# stc8g.net
KiCad netlist of a schematic drawn in EasyEDA Pro
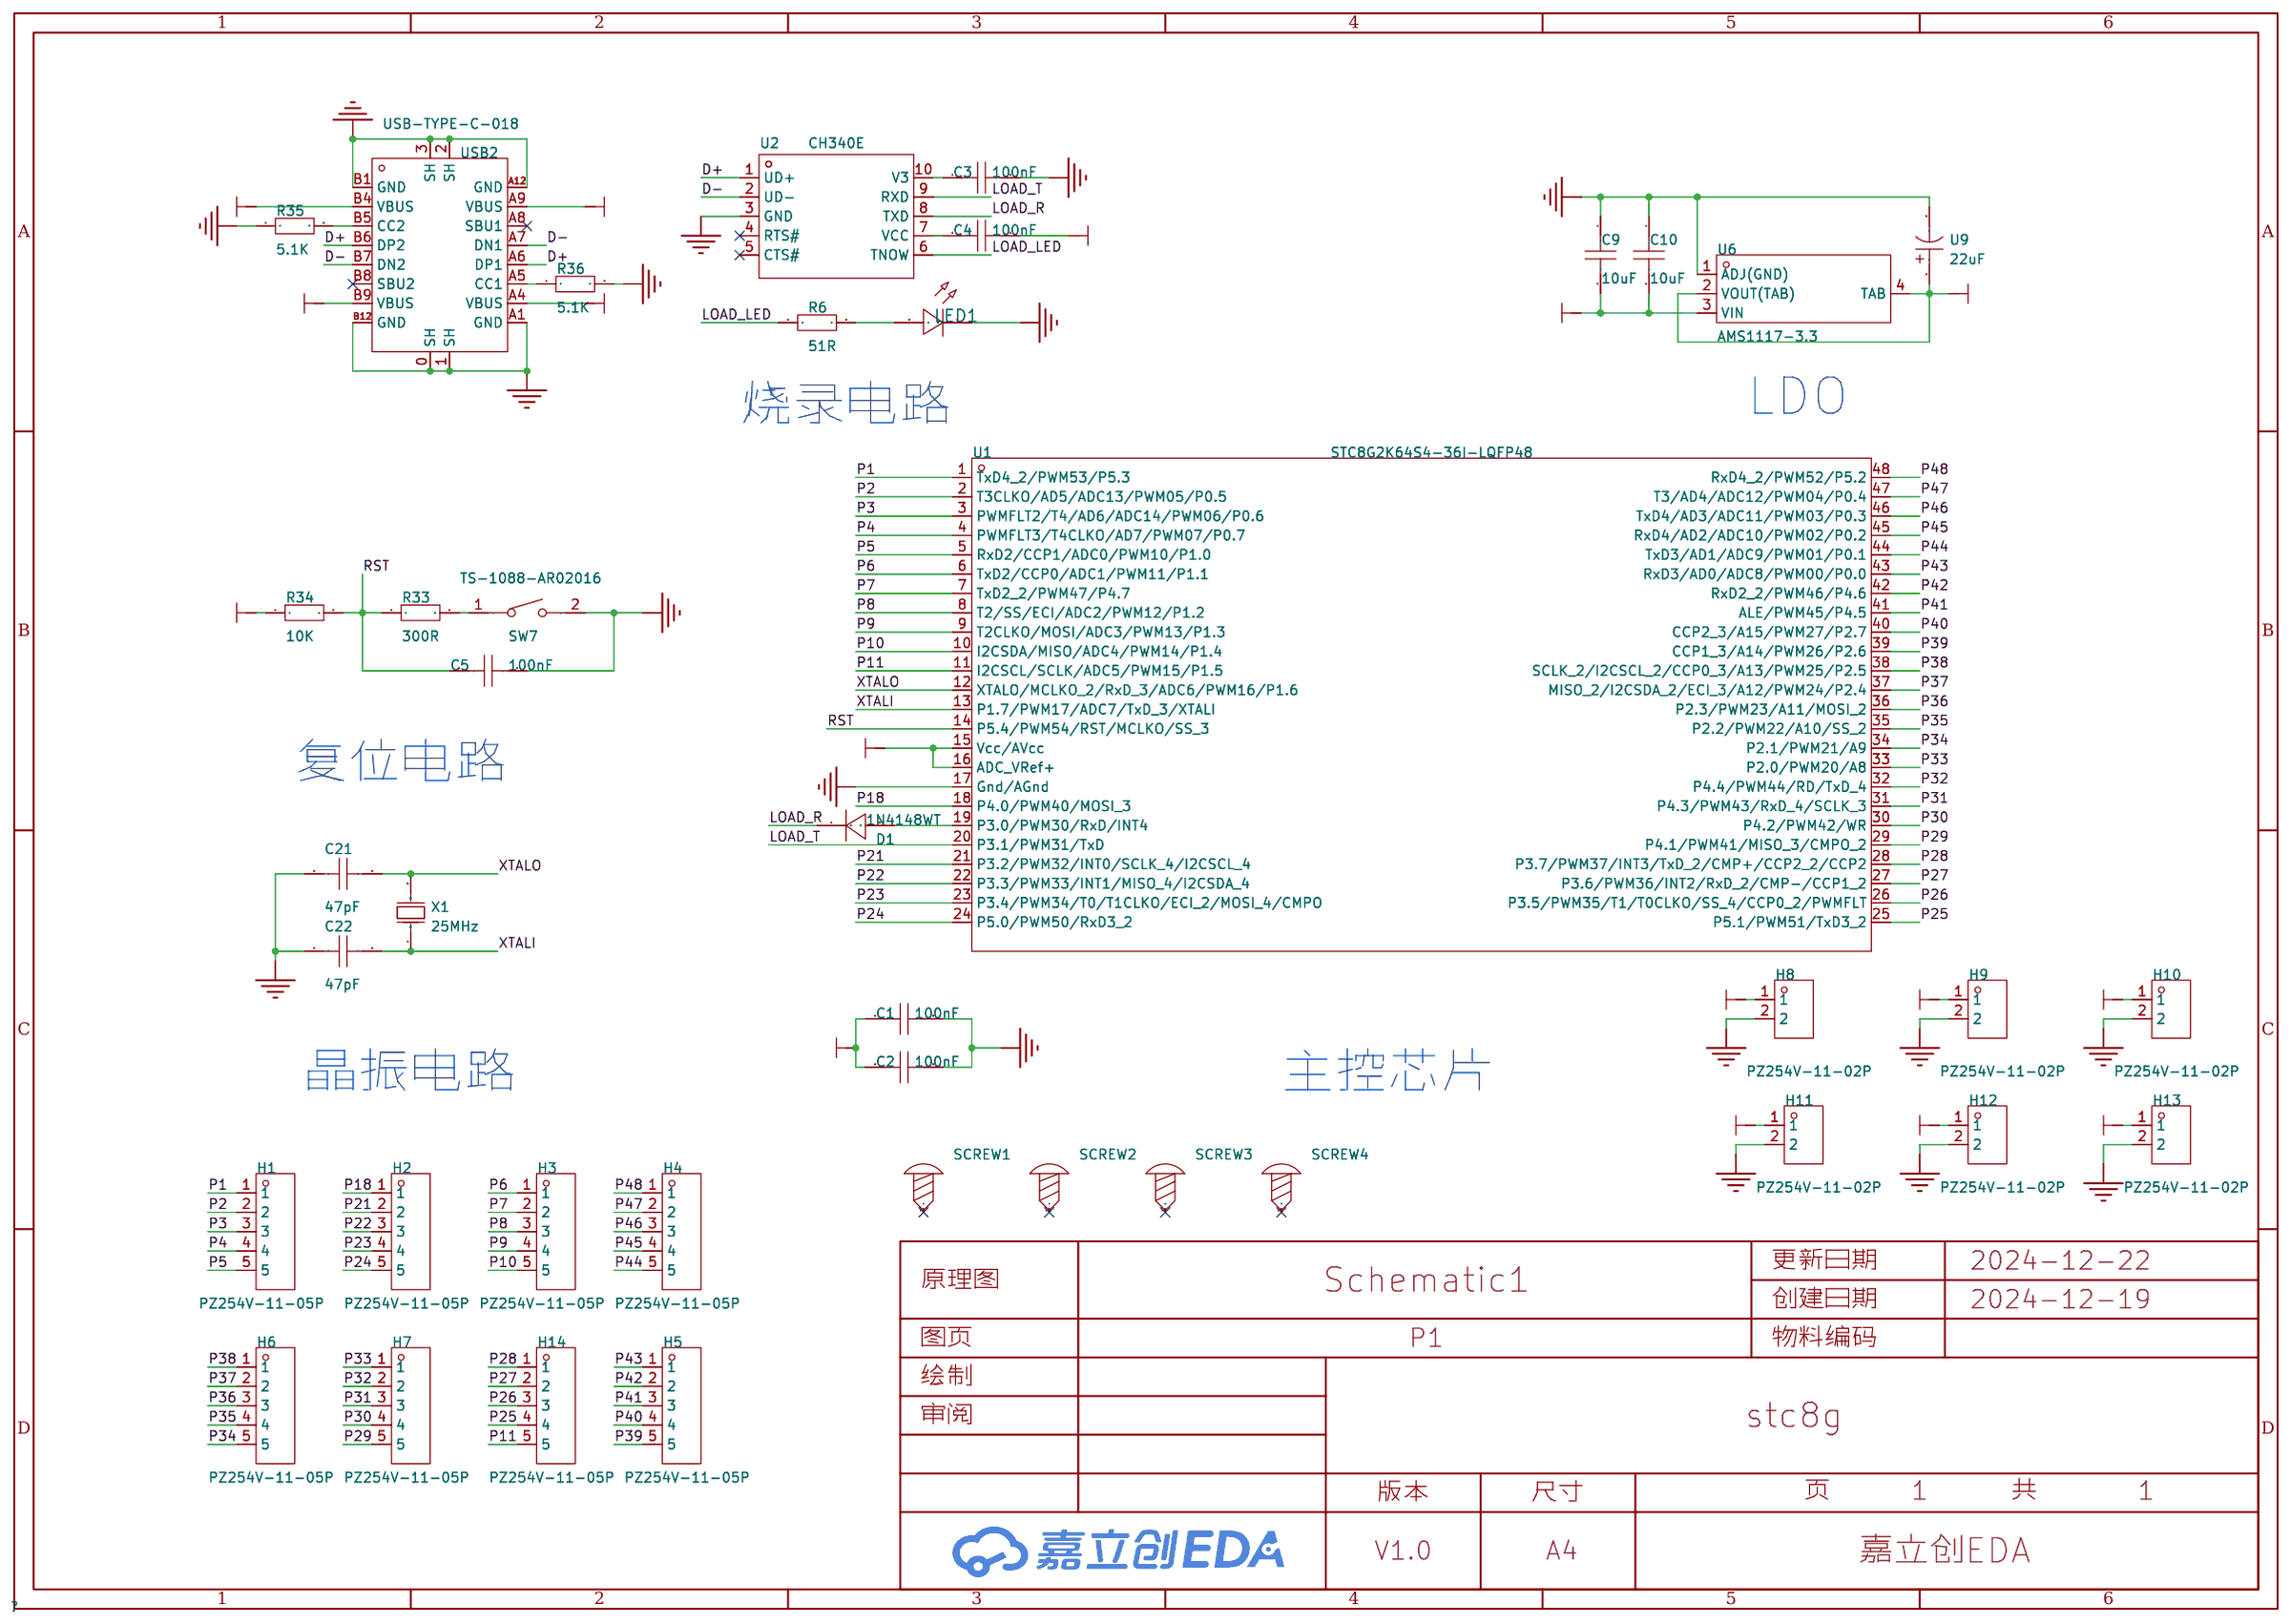
[diagram p0: schematic sheet]

(export (version "E")
  (design (tool "Eeschema 10.0.6"))
  (components
    (comp (ref "C1")
      (value "100nF")
      (footprint "easyedapro:C0603")
      (libsource (lib "easyedapro") (part "CapAcitance"))
    )
    (comp (ref "C2")
      (value "100nF")
      (footprint "easyedapro:C0603")
      (libsource (lib "easyedapro") (part "CapAcitance"))
    )
    (comp (ref "C3")
      (value "100nF")
      (footprint "easyedapro:C0603")
      (libsource (lib "easyedapro") (part "CapAcitance"))
    )
    (comp (ref "C4")
      (value "100nF")
      (footprint "easyedapro:C0603")
      (libsource (lib "easyedapro") (part "CapAcitance"))
    )
    (comp (ref "C5")
      (value "100nF")
      (footprint "easyedapro:C0603")
      (libsource (lib "easyedapro") (part "CapAcitance"))
    )
    (comp (ref "C9")
      (value "10uF")
      (footprint "easyedapro:C0603")
      (libsource (lib "easyedapro") (part "CapAcitance"))
    )
    (comp (ref "C10")
      (value "10uF")
      (footprint "easyedapro:C0603")
      (libsource (lib "easyedapro") (part "CapAcitance"))
    )
    (comp (ref "C21")
      (value "47pF")
      (footprint "easyedapro:C0603")
      (libsource (lib "easyedapro") (part "CapAcitance"))
    )
    (comp (ref "C22")
      (value "47pF")
      (footprint "easyedapro:C0603")
      (libsource (lib "easyedapro") (part "CapAcitance"))
    )
    (comp (ref "D1")
      (value "1N4148WT")
      (footprint "easyedapro:SOD-523_L1.2-W0.8-LS1.6-RD")
      (description "二极管配置:独立式;正向压降(Vf):1V@10mA;直流反向耐压(Vr):75V;平均整流电流(Io):300mA;功率:200mW;反向恢复时间(trr):4ns;")
      (fields (field (name "Manufacturer") "onsemi(安森美)"))
      (libsource (lib "easyedapro") (part "1N4148WT_C232841"))
    )
    (comp (ref "H1")
      (value "PZ254V-11-05P")
      (footprint "easyedapro:HDR-TH_5P-P2.54-V-M")
      (fields (field (name "Manufacturer") "XFCN(兴飞)"))
      (libsource (lib "easyedapro") (part "PZ254V-11-05P"))
    )
    (comp (ref "H2")
      (value "PZ254V-11-05P")
      (footprint "easyedapro:HDR-TH_5P-P2.54-V-M")
      (fields (field (name "Manufacturer") "XFCN(兴飞)"))
      (libsource (lib "easyedapro") (part "PZ254V-11-05P"))
    )
    (comp (ref "H3")
      (value "PZ254V-11-05P")
      (footprint "easyedapro:HDR-TH_5P-P2.54-V-M")
      (fields (field (name "Manufacturer") "XFCN(兴飞)"))
      (libsource (lib "easyedapro") (part "PZ254V-11-05P"))
    )
    (comp (ref "H4")
      (value "PZ254V-11-05P")
      (footprint "easyedapro:HDR-TH_5P-P2.54-V-M")
      (fields (field (name "Manufacturer") "XFCN(兴飞)"))
      (libsource (lib "easyedapro") (part "PZ254V-11-05P"))
    )
    (comp (ref "H5")
      (value "PZ254V-11-05P")
      (footprint "easyedapro:HDR-TH_5P-P2.54-V-M")
      (fields (field (name "Manufacturer") "XFCN(兴飞)"))
      (libsource (lib "easyedapro") (part "PZ254V-11-05P"))
    )
    (comp (ref "H6")
      (value "PZ254V-11-05P")
      (footprint "easyedapro:HDR-TH_5P-P2.54-V-M")
      (fields (field (name "Manufacturer") "XFCN(兴飞)"))
      (libsource (lib "easyedapro") (part "PZ254V-11-05P"))
    )
    (comp (ref "H7")
      (value "PZ254V-11-05P")
      (footprint "easyedapro:HDR-TH_5P-P2.54-V-M")
      (fields (field (name "Manufacturer") "XFCN(兴飞)"))
      (libsource (lib "easyedapro") (part "PZ254V-11-05P"))
    )
    (comp (ref "H8")
      (value "PZ254V-11-02P")
      (footprint "easyedapro:HDR-TH_2P-P2.54-V-M")
      (fields (field (name "Manufacturer") "XFCN(兴飞)"))
      (libsource (lib "easyedapro") (part "PZ254V-11-02P"))
    )
    (comp (ref "H9")
      (value "PZ254V-11-02P")
      (footprint "easyedapro:HDR-TH_2P-P2.54-V-M")
      (fields (field (name "Manufacturer") "XFCN(兴飞)"))
      (libsource (lib "easyedapro") (part "PZ254V-11-02P"))
    )
    (comp (ref "H10")
      (value "PZ254V-11-02P")
      (footprint "easyedapro:HDR-TH_2P-P2.54-V-M")
      (fields (field (name "Manufacturer") "XFCN(兴飞)"))
      (libsource (lib "easyedapro") (part "PZ254V-11-02P"))
    )
    (comp (ref "H11")
      (value "PZ254V-11-02P")
      (footprint "easyedapro:HDR-TH_2P-P2.54-V-M")
      (fields (field (name "Manufacturer") "XFCN(兴飞)"))
      (libsource (lib "easyedapro") (part "PZ254V-11-02P"))
    )
    (comp (ref "H12")
      (value "PZ254V-11-02P")
      (footprint "easyedapro:HDR-TH_2P-P2.54-V-M")
      (fields (field (name "Manufacturer") "XFCN(兴飞)"))
      (libsource (lib "easyedapro") (part "PZ254V-11-02P"))
    )
    (comp (ref "H13")
      (value "PZ254V-11-02P")
      (footprint "easyedapro:HDR-TH_2P-P2.54-V-M")
      (fields (field (name "Manufacturer") "XFCN(兴飞)"))
      (libsource (lib "easyedapro") (part "PZ254V-11-02P"))
    )
    (comp (ref "H14")
      (value "PZ254V-11-05P")
      (footprint "easyedapro:HDR-TH_5P-P2.54-V-M")
      (fields (field (name "Manufacturer") "XFCN(兴飞)"))
      (libsource (lib "easyedapro") (part "PZ254V-11-05P"))
    )
    (comp (ref "LED1")
      (value "~")
      (footprint "easyedapro:LED_0603")
      (libsource (lib "easyedapro") (part "LED_R"))
    )
    (comp (ref "R6") (value "51R") (footprint "easyedapro:R0603") (libsource (lib "easyedapro") (part "电阻")))
    (comp (ref "R33")
      (value "300R")
      (footprint "easyedapro:R0603")
      (libsource (lib "easyedapro") (part "电阻"))
    )
    (comp (ref "R34") (value "10K") (footprint "easyedapro:R0603") (libsource (lib "easyedapro") (part "电阻")))
    (comp (ref "R35")
      (value "5.1K")
      (footprint "easyedapro:R0603")
      (libsource (lib "easyedapro") (part "电阻"))
    )
    (comp (ref "R36")
      (value "5.1K")
      (footprint "easyedapro:R0603")
      (libsource (lib "easyedapro") (part "电阻"))
    )
    (comp (ref "SCREW1")
      (value "~")
      (footprint "easyedapro:M2螺丝")
      (libsource (lib "easyedapro") (part "螺丝孔"))
    )
    (comp (ref "SCREW2")
      (value "~")
      (footprint "easyedapro:M2螺丝")
      (libsource (lib "easyedapro") (part "螺丝孔"))
    )
    (comp (ref "SCREW3")
      (value "~")
      (footprint "easyedapro:M2螺丝")
      (libsource (lib "easyedapro") (part "螺丝孔"))
    )
    (comp (ref "SCREW4")
      (value "~")
      (footprint "easyedapro:M2螺丝")
      (libsource (lib "easyedapro") (part "螺丝孔"))
    )
    (comp (ref "SW7")
      (value "TS-1088-AR02016")
      (footprint "easyedapro:SW-SMD_L3.9-W3.0-P4.45")
      (fields (field (name "Manufacturer") "XUNPU(讯普)"))
      (libsource (lib "easyedapro") (part "TS-1088-AR02016"))
    )
    (comp (ref "U1")
      (value "STC8G2K64S4-36I-LQFP48")
      (footprint "easyedapro:LQFP-48_L7.0-W7.0-P0.50-LS9.0-BL")
      (description "CPU内核:51系列;程序存储容量:64KB;RAM总容量:2.25KB;GPIO端口数量:45;工作电压范围:1.9V~5.5V;CPU最大主频:-;程序存储器类型:FLASH;")
      (fields (field (name "Manufacturer") "STC(宏晶)"))
      (libsource (lib "easyedapro") (part "STC8G2K64S4-36I-LQFP48"))
    )
    (comp (ref "U2")
      (value "CH340E")
      (footprint "easyedapro:MSOP-10_L3.0-W3.0-P0.50-LS5.0-BL")
      (description "应用功能:收发器;接口协议:USB 2.0;数据速率:2Mbps;")
      (fields (field (name "Manufacturer") "WCH(南京沁恒)"))
      (libsource (lib "easyedapro") (part "CH340E"))
    )
    (comp (ref "U6")
      (value "AMS1117-3.3")
      (footprint "easyedapro:SOT-223-4_L6.5-W3.5-P2.30-LS7.0-BR")
      (description "输出类型:固定;最大输入电压:18V;输出电压:3.3V;输出电流:1A;电源纹波抑制比(PSRR):60dB@(120Hz);输出极性:正极;")
      (fields (field (name "Manufacturer") "UMW(友台半导体)"))
      (libsource (lib "easyedapro") (part "AMS1117-3.3_C347222"))
    )
    (comp (ref "U9")
      (value "22uF")
      (footprint "easyedapro:CAP-SMD_L2.0-W1.3-FD")
      (description "容值:22uF;精度:±20%;额定电压:6.3V;等效串联电阻:5.9Ω@100kHz;")
      (fields (field (name "Manufacturer Part") "TMCP0J226MTRF") (field (name "Manufacturer") "VISHAY(威世)"))
      (libsource (lib "easyedapro") (part "TMCP0J226MTRF"))
    )
    (comp (ref "USB2")
      (value "USB-TYPE-C-018")
      (footprint "easyedapro:USB-C_SMD-TYPE-C-31-M-12")
      (description "连接器类型:Type-C;标准:-;公母:母;安装方式:卧贴;触点数量:16P;端口数量:1;额定电流 - 电源:3A;工作温度范围:-25°C~+85°C;")
      (fields (field (name "Manufacturer") "DEALON(德艺隆)"))
      (libsource (lib "easyedapro") (part "USB-TYPE-C-018"))
    )
    (comp (ref "X1")
      (value "25MHz")
      (footprint "easyedapro:CRYSTAL-SMD_2P-L5.0-W3.2")
      (description "晶振类型:贴片晶振;频率:25MHz;常温频差:±10ppm;外接负载电容:20pF;频率稳定度(全温):±20ppm;")
      (fields
        (field (name "Manufacturer Part") "XG1EL89CSI-111YLC-25M")
        (field (name "Manufacturer") "YXC(扬兴晶振)")
      )
      (libsource (lib "easyedapro") (part "XG1EL89CSI-111YLC-25M"))
    )
  )
  (nets
    (net (code "1") (name "/D+") (class "Default")
      (node (ref "U2") (pin "1") (pinfunction "UD+_1") (pintype "unspecified"))
      (node (ref "USB2") (pin "A6") (pinfunction "DP1_A6") (pintype "unspecified"))
      (node (ref "USB2") (pin "B6") (pinfunction "DP2_B6") (pintype "unspecified"))
    )
    (net (code "2") (name "/D-") (class "Default")
      (node (ref "U2") (pin "2") (pinfunction "UD-_2") (pintype "unspecified"))
      (node (ref "USB2") (pin "A7") (pinfunction "DN1_A7") (pintype "unspecified"))
      (node (ref "USB2") (pin "B7") (pinfunction "DN2_B7") (pintype "unspecified"))
    )
    (net (code "3") (name "/LOAD_LED") (class "Default")
      (node (ref "R6") (pin "1") (pinfunction "1_1") (pintype "input"))
      (node (ref "U2") (pin "6") (pinfunction "TNOW_6") (pintype "unspecified"))
    )
    (net (code "4") (name "/LOAD_R") (class "Default")
      (node (ref "D1") (pin "1") (pinfunction "C_1") (pintype "unspecified"))
      (node (ref "U2") (pin "8") (pinfunction "TXD_8") (pintype "unspecified"))
    )
    (net (code "5") (name "/LOAD_T") (class "Default")
      (node (ref "U1") (pin "20") (pinfunction "P3.1/PWM31/TxD_20") (pintype "unspecified"))
      (node (ref "U2") (pin "9") (pinfunction "RXD_9") (pintype "unspecified"))
    )
    (net (code "6") (name "/P1") (class "Default")
      (node (ref "H1") (pin "1") (pinfunction "1_1") (pintype "unspecified"))
      (node (ref "U1") (pin "1") (pinfunction "TxD4_2/PWM53/P5.3_1") (pintype "unspecified"))
    )
    (net (code "7") (name "/P2") (class "Default")
      (node (ref "H1") (pin "2") (pinfunction "2_2") (pintype "unspecified"))
      (node (ref "U1") (pin "2") (pinfunction "T3CLKO/AD5/ADC13/PWM05/P0.5_2") (pintype "unspecified"))
    )
    (net (code "8") (name "/P3") (class "Default")
      (node (ref "H1") (pin "3") (pinfunction "3_3") (pintype "unspecified"))
      (node (ref "U1") (pin "3") (pinfunction "PWMFLT2/T4/AD6/ADC14/PWM06/P0.6_3") (pintype "unspecified"))
    )
    (net (code "9") (name "/P4") (class "Default")
      (node (ref "H1") (pin "4") (pinfunction "4_4") (pintype "unspecified"))
      (node (ref "U1") (pin "4") (pinfunction "PWMFLT3/T4CLKO/AD7/PWM07/P0.7_4") (pintype "unspecified"))
    )
    (net (code "10") (name "/P5") (class "Default")
      (node (ref "H1") (pin "5") (pinfunction "5_5") (pintype "unspecified"))
      (node (ref "U1") (pin "5") (pinfunction "RxD2/CCP1/ADC0/PWM10/P1.0_5") (pintype "unspecified"))
    )
    (net (code "11") (name "/P6") (class "Default")
      (node (ref "H3") (pin "1") (pinfunction "1_1") (pintype "unspecified"))
      (node (ref "U1") (pin "6") (pinfunction "TxD2/CCP0/ADC1/PWM11/P1.1_6") (pintype "unspecified"))
    )
    (net (code "12") (name "/P7") (class "Default")
      (node (ref "H3") (pin "2") (pinfunction "2_2") (pintype "unspecified"))
      (node (ref "U1") (pin "7") (pinfunction "TxD2_2/PWM47/P4.7_7") (pintype "unspecified"))
    )
    (net (code "13") (name "/P8") (class "Default")
      (node (ref "H3") (pin "3") (pinfunction "3_3") (pintype "unspecified"))
      (node (ref "U1") (pin "8") (pinfunction "T2/SS/ECI/ADC2/PWM12/P1.2_8") (pintype "unspecified"))
    )
    (net (code "14") (name "/P9") (class "Default")
      (node (ref "H3") (pin "4") (pinfunction "4_4") (pintype "unspecified"))
      (node (ref "U1") (pin "9") (pinfunction "T2CLKO/MOSI/ADC3/PWM13/P1.3_9") (pintype "unspecified"))
    )
    (net (code "15") (name "/P10") (class "Default")
      (node (ref "H3") (pin "5") (pinfunction "5_5") (pintype "unspecified"))
      (node (ref "U1") (pin "10") (pinfunction "I2CSDA/MISO/ADC4/PWM14/P1.4_10") (pintype "unspecified"))
    )
    (net (code "16") (name "/P11") (class "Default")
      (node (ref "H14") (pin "5") (pinfunction "5_5") (pintype "unspecified"))
      (node (ref "U1") (pin "11") (pinfunction "I2CSCL/SCLK/ADC5/PWM15/P1.5_11") (pintype "unspecified"))
    )
    (net (code "17") (name "/P18") (class "Default")
      (node (ref "H2") (pin "1") (pinfunction "1_1") (pintype "unspecified"))
      (node (ref "U1") (pin "18") (pinfunction "P4.0/PWM40/MOSI_3_18") (pintype "unspecified"))
    )
    (net (code "18") (name "/P21") (class "Default")
      (node (ref "H2") (pin "2") (pinfunction "2_2") (pintype "unspecified"))
      (node (ref "U1") (pin "21") (pinfunction "P3.2/PWM32/INT0/SCLK_4/I2CSCL_4_21") (pintype "unspecified"))
    )
    (net (code "19") (name "/P22") (class "Default")
      (node (ref "H2") (pin "3") (pinfunction "3_3") (pintype "unspecified"))
      (node (ref "U1") (pin "22") (pinfunction "P3.3/PWM33/INT1/MISO_4/I2CSDA_4_22") (pintype "unspecified"))
    )
    (net (code "20") (name "/P23") (class "Default")
      (node (ref "H2") (pin "4") (pinfunction "4_4") (pintype "unspecified"))
      (node (ref "U1") (pin "23") (pinfunction "P3.4/PWM34/T0/T1CLKO/ECI_2/MOSI_4/CMPO_23") (pintype "unspecified"))
    )
    (net (code "21") (name "/P24") (class "Default")
      (node (ref "H2") (pin "5") (pinfunction "5_5") (pintype "unspecified"))
      (node (ref "U1") (pin "24") (pinfunction "P5.0/PWM50/RxD3_2_24") (pintype "unspecified"))
    )
    (net (code "22") (name "/P25") (class "Default")
      (node (ref "H14") (pin "4") (pinfunction "4_4") (pintype "unspecified"))
      (node (ref "U1") (pin "25") (pinfunction "P5.1/PWM51/TxD3_2_25") (pintype "unspecified"))
    )
    (net (code "23") (name "/P26") (class "Default")
      (node (ref "H14") (pin "3") (pinfunction "3_3") (pintype "unspecified"))
      (node (ref "U1") (pin "26") (pinfunction "P3.5/PWM35/T1/T0CLKO/SS_4/CCP0_2/PWMFLT_26") (pintype "unspecified"))
    )
    (net (code "24") (name "/P27") (class "Default")
      (node (ref "H14") (pin "2") (pinfunction "2_2") (pintype "unspecified"))
      (node (ref "U1") (pin "27") (pinfunction "P3.6/PWM36/INT2/RxD_2/CMP-/CCP1_2_27") (pintype "unspecified"))
    )
    (net (code "25") (name "/P28") (class "Default")
      (node (ref "H14") (pin "1") (pinfunction "1_1") (pintype "unspecified"))
      (node (ref "U1") (pin "28") (pinfunction "P3.7/PWM37/INT3/TxD_2/CMP+/CCP2_2/CCP2_28") (pintype "unspecified"))
    )
    (net (code "26") (name "/P29") (class "Default")
      (node (ref "H7") (pin "5") (pinfunction "5_5") (pintype "unspecified"))
      (node (ref "U1") (pin "29") (pinfunction "P4.1/PWM41/MISO_3/CMPO_2_29") (pintype "unspecified"))
    )
    (net (code "27") (name "/P30") (class "Default")
      (node (ref "H7") (pin "4") (pinfunction "4_4") (pintype "unspecified"))
      (node (ref "U1") (pin "30") (pinfunction "P4.2/PWM42/WR_30") (pintype "unspecified"))
    )
    (net (code "28") (name "/P31") (class "Default")
      (node (ref "H7") (pin "3") (pinfunction "3_3") (pintype "unspecified"))
      (node (ref "U1") (pin "31") (pinfunction "P4.3/PWM43/RxD_4/SCLK_3_31") (pintype "unspecified"))
    )
    (net (code "29") (name "/P32") (class "Default")
      (node (ref "H7") (pin "2") (pinfunction "2_2") (pintype "unspecified"))
      (node (ref "U1") (pin "32") (pinfunction "P4.4/PWM44/RD/TxD_4_32") (pintype "unspecified"))
    )
    (net (code "30") (name "/P33") (class "Default")
      (node (ref "H7") (pin "1") (pinfunction "1_1") (pintype "unspecified"))
      (node (ref "U1") (pin "33") (pinfunction "P2.0/PWM20/A8_33") (pintype "unspecified"))
    )
    (net (code "31") (name "/P34") (class "Default")
      (node (ref "H6") (pin "5") (pinfunction "5_5") (pintype "unspecified"))
      (node (ref "U1") (pin "34") (pinfunction "P2.1/PWM21/A9_34") (pintype "unspecified"))
    )
    (net (code "32") (name "/P35") (class "Default")
      (node (ref "H6") (pin "4") (pinfunction "4_4") (pintype "unspecified"))
      (node (ref "U1") (pin "35") (pinfunction "P2.2/PWM22/A10/SS_2_35") (pintype "unspecified"))
    )
    (net (code "33") (name "/P36") (class "Default")
      (node (ref "H6") (pin "3") (pinfunction "3_3") (pintype "unspecified"))
      (node (ref "U1") (pin "36") (pinfunction "P2.3/PWM23/A11/MOSI_2_36") (pintype "unspecified"))
    )
    (net (code "34") (name "/P37") (class "Default")
      (node (ref "H6") (pin "2") (pinfunction "2_2") (pintype "unspecified"))
      (node (ref "U1") (pin "37") (pinfunction "MISO_2/I2CSDA_2/ECI_3/A12/PWM24/P2.4_37") (pintype "unspecified"))
    )
    (net (code "35") (name "/P38") (class "Default")
      (node (ref "H6") (pin "1") (pinfunction "1_1") (pintype "unspecified"))
      (node (ref "U1") (pin "38") (pinfunction "SCLK_2/I2CSCL_2/CCP0_3/A13/PWM25/P2.5_38") (pintype "unspecified"))
    )
    (net (code "36") (name "/P39") (class "Default")
      (node (ref "H5") (pin "5") (pinfunction "5_5") (pintype "unspecified"))
      (node (ref "U1") (pin "39") (pinfunction "CCP1_3/A14/PWM26/P2.6_39") (pintype "unspecified"))
    )
    (net (code "37") (name "/P40") (class "Default")
      (node (ref "H5") (pin "4") (pinfunction "4_4") (pintype "unspecified"))
      (node (ref "U1") (pin "40") (pinfunction "CCP2_3/A15/PWM27/P2.7_40") (pintype "unspecified"))
    )
    (net (code "38") (name "/P41") (class "Default")
      (node (ref "H5") (pin "3") (pinfunction "3_3") (pintype "unspecified"))
      (node (ref "U1") (pin "41") (pinfunction "ALE/PWM45/P4.5_41") (pintype "unspecified"))
    )
    (net (code "39") (name "/P42") (class "Default")
      (node (ref "H5") (pin "2") (pinfunction "2_2") (pintype "unspecified"))
      (node (ref "U1") (pin "42") (pinfunction "RxD2_2/PWM46/P4.6_42") (pintype "unspecified"))
    )
    (net (code "40") (name "/P43") (class "Default")
      (node (ref "H5") (pin "1") (pinfunction "1_1") (pintype "unspecified"))
      (node (ref "U1") (pin "43") (pinfunction "RxD3/AD0/ADC8/PWM00/P0.0_43") (pintype "unspecified"))
    )
    (net (code "41") (name "/P44") (class "Default")
      (node (ref "H4") (pin "5") (pinfunction "5_5") (pintype "unspecified"))
      (node (ref "U1") (pin "44") (pinfunction "TxD3/AD1/ADC9/PWM01/P0.1_44") (pintype "unspecified"))
    )
    (net (code "42") (name "/P45") (class "Default")
      (node (ref "H4") (pin "4") (pinfunction "4_4") (pintype "unspecified"))
      (node (ref "U1") (pin "45") (pinfunction "RxD4/AD2/ADC10/PWM02/P0.2_45") (pintype "unspecified"))
    )
    (net (code "43") (name "/P46") (class "Default")
      (node (ref "H4") (pin "3") (pinfunction "3_3") (pintype "unspecified"))
      (node (ref "U1") (pin "46") (pinfunction "TxD4/AD3/ADC11/PWM03/P0.3_46") (pintype "unspecified"))
    )
    (net (code "44") (name "/P47") (class "Default")
      (node (ref "H4") (pin "2") (pinfunction "2_2") (pintype "unspecified"))
      (node (ref "U1") (pin "47") (pinfunction "T3/AD4/ADC12/PWM04/P0.4_47") (pintype "unspecified"))
    )
    (net (code "45") (name "/P48") (class "Default")
      (node (ref "H4") (pin "1") (pinfunction "1_1") (pintype "unspecified"))
      (node (ref "U1") (pin "48") (pinfunction "RxD4_2/PWM52/P5.2_48") (pintype "unspecified"))
    )
    (net (code "46") (name "/RST") (class "Default")
      (node (ref "C5") (pin "2") (pinfunction "2_2") (pintype "input"))
      (node (ref "R33") (pin "1") (pinfunction "1_1") (pintype "input"))
      (node (ref "R34") (pin "2") (pinfunction "2_2") (pintype "input"))
      (node (ref "U1") (pin "14") (pinfunction "P5.4/PWM54/RST/MCLKO/SS_3_14") (pintype "unspecified"))
    )
    (net (code "47") (name "/XTALI") (class "Default")
      (node (ref "C22") (pin "2") (pinfunction "2_2") (pintype "input"))
      (node (ref "U1") (pin "13") (pinfunction "P1.7/PWM17/ADC7/TxD_3/XTALI_13") (pintype "unspecified"))
      (node (ref "X1") (pin "1") (pinfunction "OSC1_1") (pintype "input"))
    )
    (net (code "48") (name "/XTALO") (class "Default")
      (node (ref "C21") (pin "2") (pinfunction "2_2") (pintype "input"))
      (node (ref "U1") (pin "12") (pinfunction "XTALO/MCLKO_2/RxD_3/ADC6/PWM16/P1.6_12") (pintype "unspecified"))
      (node (ref "X1") (pin "2") (pinfunction "OSC2_2") (pintype "input"))
    )
    (net (code "49") (name "3V3") (class "Default")
      (node (ref "C1") (pin "1") (pinfunction "1_1") (pintype "input"))
      (node (ref "C2") (pin "1") (pinfunction "1_1") (pintype "input"))
      (node (ref "H10") (pin "1") (pinfunction "1_1") (pintype "unspecified"))
      (node (ref "H11") (pin "1") (pinfunction "1_1") (pintype "unspecified"))
      (node (ref "H12") (pin "1") (pinfunction "1_1") (pintype "unspecified"))
      (node (ref "H13") (pin "1") (pinfunction "1_1") (pintype "unspecified"))
      (node (ref "H8") (pin "1") (pinfunction "1_1") (pintype "unspecified"))
      (node (ref "H9") (pin "1") (pinfunction "1_1") (pintype "unspecified"))
      (node (ref "R34") (pin "1") (pinfunction "1_1") (pintype "input"))
      (node (ref "U1") (pin "15") (pinfunction "Vcc/AVcc_15") (pintype "unspecified"))
      (node (ref "U1") (pin "16") (pinfunction "ADC_VRef+_16") (pintype "unspecified"))
      (node (ref "U6") (pin "2") (pinfunction "VOUT(TAB)_2") (pintype "unspecified"))
      (node (ref "U6") (pin "4") (pinfunction "TAB_4") (pintype "unspecified"))
      (node (ref "U9") (pin "1") (pinfunction "1_1") (pintype "input"))
    )
    (net (code "50") (name "GND") (class "Default")
      (node (ref "C1") (pin "2") (pinfunction "2_2") (pintype "input"))
      (node (ref "C10") (pin "1") (pinfunction "1_1") (pintype "input"))
      (node (ref "C2") (pin "2") (pinfunction "2_2") (pintype "input"))
      (node (ref "C21") (pin "1") (pinfunction "1_1") (pintype "input"))
      (node (ref "C22") (pin "1") (pinfunction "1_1") (pintype "input"))
      (node (ref "C3") (pin "2") (pinfunction "2_2") (pintype "input"))
      (node (ref "C5") (pin "1") (pinfunction "1_1") (pintype "input"))
      (node (ref "C9") (pin "1") (pinfunction "1_1") (pintype "input"))
      (node (ref "H10") (pin "2") (pinfunction "2_2") (pintype "unspecified"))
      (node (ref "H11") (pin "2") (pinfunction "2_2") (pintype "unspecified"))
      (node (ref "H12") (pin "2") (pinfunction "2_2") (pintype "unspecified"))
      (node (ref "H13") (pin "2") (pinfunction "2_2") (pintype "unspecified"))
      (node (ref "H8") (pin "2") (pinfunction "2_2") (pintype "unspecified"))
      (node (ref "H9") (pin "2") (pinfunction "2_2") (pintype "unspecified"))
      (node (ref "LED1") (pin "1") (pinfunction "C_1") (pintype "input"))
      (node (ref "R35") (pin "1") (pinfunction "1_1") (pintype "input"))
      (node (ref "R36") (pin "2") (pinfunction "2_2") (pintype "input"))
      (node (ref "SW7") (pin "2") (pinfunction "2_2") (pintype "unspecified"))
      (node (ref "U1") (pin "17") (pinfunction "Gnd/AGnd_17") (pintype "unspecified"))
      (node (ref "U2") (pin "3") (pinfunction "GND_3") (pintype "unspecified"))
      (node (ref "U6") (pin "1") (pinfunction "ADJ(GND)_1") (pintype "unspecified"))
      (node (ref "U9") (pin "2") (pinfunction "2_2") (pintype "input"))
      (node (ref "USB2") (pin "0") (pinfunction "SH_0") (pintype "unspecified"))
      (node (ref "USB2") (pin "1") (pinfunction "SH_1") (pintype "unspecified"))
      (node (ref "USB2") (pin "2") (pinfunction "SH_2") (pintype "unspecified"))
      (node (ref "USB2") (pin "3") (pinfunction "SH_3") (pintype "unspecified"))
      (node (ref "USB2") (pin "A1") (pinfunction "GND_A1") (pintype "unspecified"))
      (node (ref "USB2") (pin "A12") (pinfunction "GND_A12") (pintype "unspecified"))
      (node (ref "USB2") (pin "B1") (pinfunction "GND_B1") (pintype "unspecified"))
      (node (ref "USB2") (pin "B12") (pinfunction "GND_B12") (pintype "unspecified"))
    )
    (net (code "51") (name "Net-(D1-A)") (class "Default")
      (node (ref "D1") (pin "2") (pinfunction "A_2") (pintype "unspecified"))
      (node (ref "U1") (pin "19") (pinfunction "P3.0/PWM30/RxD/INT4_19") (pintype "unspecified"))
    )
    (net (code "52") (name "Net-(LED1-A)") (class "Default")
      (node (ref "LED1") (pin "2") (pinfunction "A_2") (pintype "input"))
      (node (ref "R6") (pin "2") (pinfunction "2_2") (pintype "input"))
    )
    (net (code "53") (name "Net-(R33-Pad2)") (class "Default")
      (node (ref "R33") (pin "2") (pinfunction "2_2") (pintype "input"))
      (node (ref "SW7") (pin "1") (pinfunction "1_1") (pintype "unspecified"))
    )
    (net (code "54") (name "Net-(U2-V3)") (class "Default")
      (node (ref "C3") (pin "1") (pinfunction "1_1") (pintype "input"))
      (node (ref "U2") (pin "10") (pinfunction "V3_10") (pintype "unspecified"))
    )
    (net (code "55") (name "Net-(U2-VCC)") (class "Default")
      (node (ref "C4") (pin "2") (pinfunction "2_2") (pintype "input"))
      (node (ref "U2") (pin "7") (pinfunction "VCC_7") (pintype "unspecified"))
    )
    (net (code "56") (name "Net-(USB2-CC1)") (class "Default")
      (node (ref "R36") (pin "1") (pinfunction "1_1") (pintype "input"))
      (node (ref "USB2") (pin "A5") (pinfunction "CC1_A5") (pintype "unspecified"))
    )
    (net (code "57") (name "Net-(USB2-CC2)") (class "Default")
      (node (ref "R35") (pin "2") (pinfunction "2_2") (pintype "input"))
      (node (ref "USB2") (pin "B5") (pinfunction "CC2_B5") (pintype "unspecified"))
    )
    (net (code "58") (name "VBUS") (class "Default")
      (node (ref "C10") (pin "2") (pinfunction "2_2") (pintype "input"))
      (node (ref "C4") (pin "1") (pinfunction "1_1") (pintype "input"))
      (node (ref "C9") (pin "2") (pinfunction "2_2") (pintype "input"))
      (node (ref "U6") (pin "3") (pinfunction "VIN_3") (pintype "unspecified"))
      (node (ref "USB2") (pin "A4") (pinfunction "VBUS_A4") (pintype "unspecified"))
      (node (ref "USB2") (pin "A9") (pinfunction "VBUS_A9") (pintype "unspecified"))
      (node (ref "USB2") (pin "B4") (pinfunction "VBUS_B4") (pintype "unspecified"))
      (node (ref "USB2") (pin "B9") (pinfunction "VBUS_B9") (pintype "unspecified"))
    )
    (net (code "59") (name "unconnected-(SCREW1-Pad1)") (class "Default")
      (node (ref "SCREW1") (pin "1") (pinfunction "1_1") (pintype "input+no_connect"))
    )
    (net (code "60") (name "unconnected-(SCREW2-Pad1)") (class "Default")
      (node (ref "SCREW2") (pin "1") (pinfunction "1_1") (pintype "input+no_connect"))
    )
    (net (code "61") (name "unconnected-(SCREW3-Pad1)") (class "Default")
      (node (ref "SCREW3") (pin "1") (pinfunction "1_1") (pintype "input+no_connect"))
    )
    (net (code "62") (name "unconnected-(SCREW4-Pad1)") (class "Default")
      (node (ref "SCREW4") (pin "1") (pinfunction "1_1") (pintype "input+no_connect"))
    )
    (net (code "63") (name "unconnected-(U2-CTS#-Pad5)") (class "Default")
      (node (ref "U2") (pin "5") (pinfunction "CTS#_5") (pintype "unspecified+no_connect"))
    )
    (net (code "64") (name "unconnected-(U2-RTS#-Pad4)") (class "Default")
      (node (ref "U2") (pin "4") (pinfunction "RTS#_4") (pintype "unspecified+no_connect"))
    )
    (net (code "65") (name "unconnected-(USB2-SBU1-PadA8)") (class "Default")
      (node (ref "USB2") (pin "A8") (pinfunction "SBU1_A8") (pintype "unspecified+no_connect"))
    )
    (net (code "66") (name "unconnected-(USB2-SBU2-PadB8)") (class "Default")
      (node (ref "USB2") (pin "B8") (pinfunction "SBU2_B8") (pintype "unspecified+no_connect"))
    )
  )
)
